# BMD-200_eval.net
KiCad netlist of a schematic drawn in EAGLE
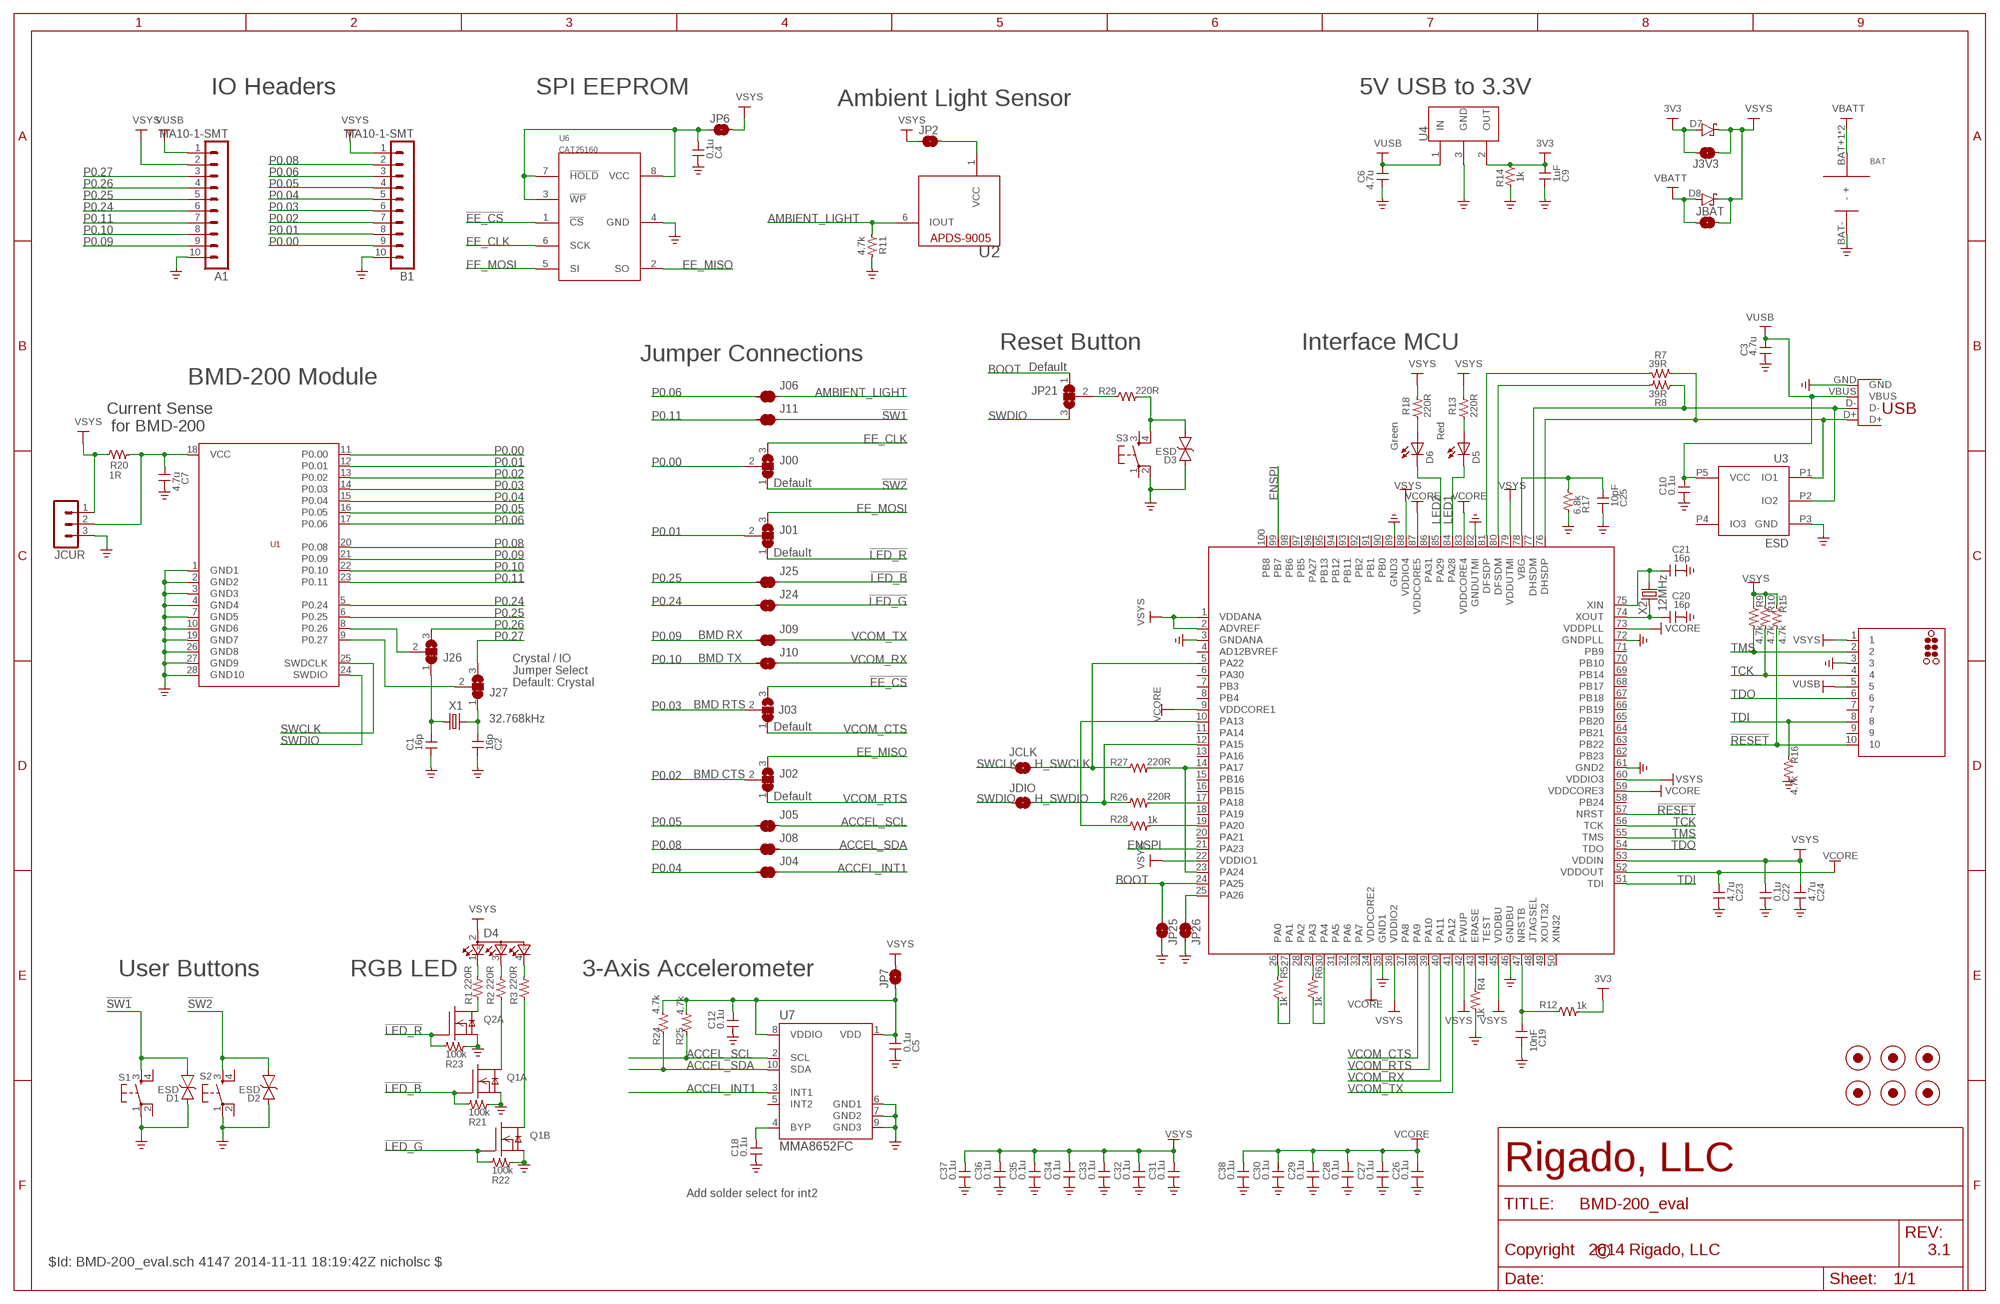
[diagram p0: schematic, sheet 1]

(export (version "E")
  (design (tool "Eeschema 10.0.6"))
  (components
    (comp (ref "A1")
      (value "MA10-1-SMT")
      (footprint "eagle-import:MA10-A-SMT")
      (description "10 SIL VERT SMT HDR")
      (fields (field (name "MFR") "Harwin"))
      (libsource (lib "eagle-import") (part "MA10-1-SMT"))
    )
    (comp (ref "B1")
      (value "MA10-1-SMT")
      (footprint "eagle-import:MA10-A-SMT")
      (description "10 SIL VERT SMT HDR")
      (fields (field (name "MFR") "Harwin"))
      (libsource (lib "eagle-import") (part "MA10-1-SMT"))
    )
    (comp (ref "BAT")
      (value "COINCELL-1")
      (footprint "eagle-import:CR2032-1")
      (description "Battery Holders, Clips & Contacts Linx CR2032 Battery Holder")
      (fields (field (name "MFR") "Linx"))
      (libsource (lib "eagle-import") (part "COINCELL-1"))
    )
    (comp (ref "C1")
      (value "16p")
      (footprint "eagle-import:SMD0402")
      (description "CAP CER 16PF 50V 5% NP0 0402")
      (fields (field (name "MFR") "Samsung"))
      (libsource (lib "eagle-import") (part "C-0402"))
    )
    (comp (ref "C2")
      (value "16p")
      (footprint "eagle-import:SMD0402")
      (description "CAP CER 16PF 50V 5% NP0 0402")
      (fields (field (name "MFR") "Samsung"))
      (libsource (lib "eagle-import") (part "C-0402"))
    )
    (comp (ref "C3")
      (value "4.7u")
      (footprint "eagle-import:SMD0603")
      (description "CAP CER 4.7UF 6.3V 10% X5R 0603")
      (fields (field (name "MFR") "Murata"))
      (libsource (lib "eagle-import") (part "C-0603"))
    )
    (comp (ref "C4")
      (value "0.1u")
      (footprint "eagle-import:SMD0402")
      (description "CAP CER 0.1UF 6.3V 10% X5R 0402")
      (fields (field (name "MFR") "Samsung"))
      (libsource (lib "eagle-import") (part "C-0402"))
    )
    (comp (ref "C5")
      (value "0.1u")
      (footprint "eagle-import:SMD0402")
      (description "CAP CER 0.1UF 6.3V 10% X5R 0402")
      (fields (field (name "MFR") "Samsung"))
      (libsource (lib "eagle-import") (part "C-0402"))
    )
    (comp (ref "C6")
      (value "4.7u")
      (footprint "eagle-import:SMD0603")
      (description "CAP CER 4.7UF 6.3V 10% X5R 0603")
      (fields (field (name "MFR") "Murata"))
      (libsource (lib "eagle-import") (part "C-0603"))
    )
    (comp (ref "C7")
      (value "4.7u")
      (footprint "eagle-import:SMD0603")
      (description "CAP CER 4.7UF 6.3V 10% X5R 0603")
      (fields (field (name "MFR") "Murata"))
      (libsource (lib "eagle-import") (part "C-0603"))
    )
    (comp (ref "C9")
      (value "1uF")
      (footprint "eagle-import:SMD0402")
      (description "CAP CER 1UF 6.3V 5% X5R 0402")
      (fields (field (name "MFR") "Samsung"))
      (libsource (lib "eagle-import") (part "C-0402"))
    )
    (comp (ref "C10")
      (value "0.1u")
      (footprint "eagle-import:SMD0402")
      (description "CAP CER 0.1UF 6.3V 10% X5R 0402")
      (fields (field (name "MFR") "Samsung"))
      (libsource (lib "eagle-import") (part "C-0402"))
    )
    (comp (ref "C12")
      (value "0.1u")
      (footprint "eagle-import:SMD0402")
      (description "CAP CER 0.1UF 6.3V 10% X5R 0402")
      (fields (field (name "MFR") "Samsung"))
      (libsource (lib "eagle-import") (part "C-0402"))
    )
    (comp (ref "C18")
      (value "0.1u")
      (footprint "eagle-import:SMD0402")
      (description "CAP CER 0.1UF 6.3V 10% X5R 0402")
      (fields (field (name "MFR") "Samsung"))
      (libsource (lib "eagle-import") (part "C-0402"))
    )
    (comp (ref "C19")
      (value "10nF")
      (footprint "eagle-import:SMD0402")
      (description "CAP CER 10000PF 16V 10% X7R 0402")
      (fields (field (name "MFR") "Samsung"))
      (libsource (lib "eagle-import") (part "C-0402"))
    )
    (comp (ref "C20")
      (value "16p")
      (footprint "eagle-import:SMD0402")
      (description "CAP CER 16PF 50V 5% NP0 0402")
      (fields (field (name "MFR") "Samsung"))
      (libsource (lib "eagle-import") (part "C-0402"))
    )
    (comp (ref "C21")
      (value "16p")
      (footprint "eagle-import:SMD0402")
      (description "CAP CER 16PF 50V 5% NP0 0402")
      (fields (field (name "MFR") "Samsung"))
      (libsource (lib "eagle-import") (part "C-0402"))
    )
    (comp (ref "C22")
      (value "0.1u")
      (footprint "eagle-import:SMD0402")
      (description "CAP CER 0.1UF 6.3V 10% X5R 0402")
      (fields (field (name "MFR") "Samsung"))
      (libsource (lib "eagle-import") (part "C-0402"))
    )
    (comp (ref "C23")
      (value "4.7u")
      (footprint "eagle-import:SMD0603")
      (description "CAP CER 4.7UF 6.3V 10% X5R 0603")
      (fields (field (name "MFR") "Murata"))
      (libsource (lib "eagle-import") (part "C-0603"))
    )
    (comp (ref "C24")
      (value "4.7u")
      (footprint "eagle-import:SMD0603")
      (description "CAP CER 4.7UF 6.3V 10% X5R 0603")
      (fields (field (name "MFR") "Murata"))
      (libsource (lib "eagle-import") (part "C-0603"))
    )
    (comp (ref "C25")
      (value "10pF")
      (footprint "eagle-import:SMD0402")
      (description "CAP CER 10PF 50V 5% NP0 0402")
      (fields (field (name "MFR") "Samsung"))
      (libsource (lib "eagle-import") (part "C-0402"))
    )
    (comp (ref "C26")
      (value "0.1u")
      (footprint "eagle-import:SMD0402")
      (description "CAP CER 0.1UF 6.3V 10% X5R 0402")
      (fields (field (name "MFR") "Samsung"))
      (libsource (lib "eagle-import") (part "C-0402"))
    )
    (comp (ref "C27")
      (value "0.1u")
      (footprint "eagle-import:SMD0402")
      (description "CAP CER 0.1UF 6.3V 10% X5R 0402")
      (fields (field (name "MFR") "Samsung"))
      (libsource (lib "eagle-import") (part "C-0402"))
    )
    (comp (ref "C28")
      (value "0.1u")
      (footprint "eagle-import:SMD0402")
      (description "CAP CER 0.1UF 6.3V 10% X5R 0402")
      (fields (field (name "MFR") "Samsung"))
      (libsource (lib "eagle-import") (part "C-0402"))
    )
    (comp (ref "C29")
      (value "0.1u")
      (footprint "eagle-import:SMD0402")
      (description "CAP CER 0.1UF 6.3V 10% X5R 0402")
      (fields (field (name "MFR") "Samsung"))
      (libsource (lib "eagle-import") (part "C-0402"))
    )
    (comp (ref "C30")
      (value "0.1u")
      (footprint "eagle-import:SMD0402")
      (description "CAP CER 0.1UF 6.3V 10% X5R 0402")
      (fields (field (name "MFR") "Samsung"))
      (libsource (lib "eagle-import") (part "C-0402"))
    )
    (comp (ref "C31")
      (value "0.1u")
      (footprint "eagle-import:SMD0402")
      (description "CAP CER 0.1UF 6.3V 10% X5R 0402")
      (fields (field (name "MFR") "Samsung"))
      (libsource (lib "eagle-import") (part "C-0402"))
    )
    (comp (ref "C32")
      (value "0.1u")
      (footprint "eagle-import:SMD0402")
      (description "CAP CER 0.1UF 6.3V 10% X5R 0402")
      (fields (field (name "MFR") "Samsung"))
      (libsource (lib "eagle-import") (part "C-0402"))
    )
    (comp (ref "C33")
      (value "0.1u")
      (footprint "eagle-import:SMD0402")
      (description "CAP CER 0.1UF 6.3V 10% X5R 0402")
      (fields (field (name "MFR") "Samsung"))
      (libsource (lib "eagle-import") (part "C-0402"))
    )
    (comp (ref "C34")
      (value "0.1u")
      (footprint "eagle-import:SMD0402")
      (description "CAP CER 0.1UF 6.3V 10% X5R 0402")
      (fields (field (name "MFR") "Samsung"))
      (libsource (lib "eagle-import") (part "C-0402"))
    )
    (comp (ref "C35")
      (value "0.1u")
      (footprint "eagle-import:SMD0402")
      (description "CAP CER 0.1UF 6.3V 10% X5R 0402")
      (fields (field (name "MFR") "Samsung"))
      (libsource (lib "eagle-import") (part "C-0402"))
    )
    (comp (ref "C36")
      (value "0.1u")
      (footprint "eagle-import:SMD0402")
      (description "CAP CER 0.1UF 6.3V 10% X5R 0402")
      (fields (field (name "MFR") "Samsung"))
      (libsource (lib "eagle-import") (part "C-0402"))
    )
    (comp (ref "C37")
      (value "0.1u")
      (footprint "eagle-import:SMD0402")
      (description "CAP CER 0.1UF 6.3V 10% X5R 0402")
      (fields (field (name "MFR") "Samsung"))
      (libsource (lib "eagle-import") (part "C-0402"))
    )
    (comp (ref "C38")
      (value "0.1u")
      (footprint "eagle-import:SMD0402")
      (description "CAP CER 0.1UF 6.3V 10% X5R 0402")
      (fields (field (name "MFR") "Samsung"))
      (libsource (lib "eagle-import") (part "C-0402"))
    )
    (comp (ref "D1")
      (value "ESD")
      (footprint "eagle-import:SOD-923")
      (description "TVS DIODE 3.3VWM SOD923")
      (fields
        (field (name "EACH") "0.04234")
        (field (name "MFPN") "ESD9B3.3ST5G")
        (field (name "MFR") "On Semi")
        (field (name "VEND") "Digikey")
        (field (name "VPN") "ESD9B3.3ST5GOSCT-ND")
      )
      (libsource (lib "eagle-import") (part "ESDSOD-923"))
    )
    (comp (ref "D2")
      (value "ESD")
      (footprint "eagle-import:SOD-923")
      (description "TVS DIODE 3.3VWM SOD923")
      (fields
        (field (name "EACH") "0.04234")
        (field (name "MFPN") "ESD9B3.3ST5G")
        (field (name "MFR") "On Semi")
        (field (name "VEND") "Digikey")
        (field (name "VPN") "ESD9B3.3ST5GOSCT-ND")
      )
      (libsource (lib "eagle-import") (part "ESDSOD-923"))
    )
    (comp (ref "D3")
      (value "ESD")
      (footprint "eagle-import:SOD-923")
      (description "TVS DIODE 3.3VWM SOD923")
      (fields
        (field (name "EACH") "0.04234")
        (field (name "MFPN") "ESD9B3.3ST5G")
        (field (name "MFR") "On Semi")
        (field (name "VEND") "Digikey")
        (field (name "VPN") "ESD9B3.3ST5GOSCT-ND")
      )
      (libsource (lib "eagle-import") (part "ESDSOD-923"))
    )
    (comp (ref "D4")
      (value "RGD_LED")
      (footprint "eagle-import:P-LLC-4-SMALL")
      (description "LED RGB SMD DIFF 4-PLCC")
      (fields (field (name "MFR") "Cree"))
      (libsource (lib "eagle-import") (part "TOPLED-3-MIN"))
    )
    (comp (ref "D5")
      (value "Red")
      (footprint "eagle-import:LED0603")
      (description "LED 1.6X0.8MM 625NM RED CLR SMD")
      (fields (field (name "MFR") "Kingbright"))
      (libsource (lib "eagle-import") (part "LED-0603"))
    )
    (comp (ref "D6")
      (value "Green")
      (footprint "eagle-import:LED0603")
      (description "LED 1.6X0.8MM 568NM GRN CLR SMD")
      (fields (field (name "MFR") "Kingbright"))
      (libsource (lib "eagle-import") (part "LED-0603"))
    )
    (comp (ref "D7")
      (value "D-SCHOTTKY-SOD-123")
      (footprint "eagle-import:SOD-123")
      (description "DIODE SCHOTTKY 20V 0.5A SOD123")
      (fields (field (name "MFR") "ON Semi"))
      (libsource (lib "eagle-import") (part "D-SCHOTTKY-SOD-123"))
    )
    (comp (ref "D8")
      (value "D-SCHOTTKY-SOD-123")
      (footprint "eagle-import:SOD-123")
      (description "DIODE SCHOTTKY 20V 0.5A SOD123")
      (fields (field (name "MFR") "ON Semi"))
      (libsource (lib "eagle-import") (part "D-SCHOTTKY-SOD-123"))
    )
    (comp (ref "FID1")
      (value "FIDUCIAL-.04")
      (footprint "eagle-import:FIDUCIAL-.04")
      (libsource (lib "eagle-import") (part "FIDUCIAL-.04"))
    )
    (comp (ref "FID2")
      (value "FIDUCIAL-.04")
      (footprint "eagle-import:FIDUCIAL-.04")
      (libsource (lib "eagle-import") (part "FIDUCIAL-.04"))
    )
    (comp (ref "FID3")
      (value "FIDUCIAL-.04")
      (footprint "eagle-import:FIDUCIAL-.04")
      (libsource (lib "eagle-import") (part "FIDUCIAL-.04"))
    )
    (comp (ref "FID4")
      (value "FIDUCIAL-.04")
      (footprint "eagle-import:FIDUCIAL-.04")
      (libsource (lib "eagle-import") (part "FIDUCIAL-.04"))
    )
    (comp (ref "FID5")
      (value "FIDUCIAL-.04")
      (footprint "eagle-import:FIDUCIAL-.04")
      (libsource (lib "eagle-import") (part "FIDUCIAL-.04"))
    )
    (comp (ref "FID6")
      (value "FIDUCIAL-.04")
      (footprint "eagle-import:FIDUCIAL-.04")
      (libsource (lib "eagle-import") (part "FIDUCIAL-.04"))
    )
    (comp (ref "J00")
      (value "SOLDER_JUMPER_2WAY-TRACE12")
      (footprint "eagle-import:SJ_2WAY_TRACE")
      (libsource (lib "eagle-import") (part "SOLDER_JUMPER_2WAY-TRACE12"))
    )
    (comp (ref "J01")
      (value "SOLDER_JUMPER_2WAY-TRACE12")
      (footprint "eagle-import:SJ_2WAY_TRACE")
      (libsource (lib "eagle-import") (part "SOLDER_JUMPER_2WAY-TRACE12"))
    )
    (comp (ref "J02")
      (value "SOLDER_JUMPER_2WAY-TRACE12")
      (footprint "eagle-import:SJ_2WAY_TRACE")
      (libsource (lib "eagle-import") (part "SOLDER_JUMPER_2WAY-TRACE12"))
    )
    (comp (ref "J03")
      (value "SOLDER_JUMPER_2WAY-TRACE12")
      (footprint "eagle-import:SJ_2WAY_TRACE")
      (libsource (lib "eagle-import") (part "SOLDER_JUMPER_2WAY-TRACE12"))
    )
    (comp (ref "J3V3")
      (value "SOLDER_JUMPER")
      (footprint "eagle-import:SJ_2")
      (libsource (lib "eagle-import") (part "SOLDER_JUMPER"))
    )
    (comp (ref "J04")
      (value "SOLDER_JUMPER-TRACE")
      (footprint "eagle-import:SJ_2_TRACE")
      (libsource (lib "eagle-import") (part "SOLDER_JUMPER-TRACE"))
    )
    (comp (ref "J05")
      (value "SOLDER_JUMPER-TRACE")
      (footprint "eagle-import:SJ_2_TRACE")
      (libsource (lib "eagle-import") (part "SOLDER_JUMPER-TRACE"))
    )
    (comp (ref "J06")
      (value "SOLDER_JUMPER-TRACE")
      (footprint "eagle-import:SJ_2_TRACE")
      (libsource (lib "eagle-import") (part "SOLDER_JUMPER-TRACE"))
    )
    (comp (ref "J08")
      (value "SOLDER_JUMPER-TRACE")
      (footprint "eagle-import:SJ_2_TRACE")
      (libsource (lib "eagle-import") (part "SOLDER_JUMPER-TRACE"))
    )
    (comp (ref "J09")
      (value "SOLDER_JUMPER-TRACE")
      (footprint "eagle-import:SJ_2_TRACE")
      (libsource (lib "eagle-import") (part "SOLDER_JUMPER-TRACE"))
    )
    (comp (ref "J10")
      (value "SOLDER_JUMPER-TRACE")
      (footprint "eagle-import:SJ_2_TRACE")
      (libsource (lib "eagle-import") (part "SOLDER_JUMPER-TRACE"))
    )
    (comp (ref "J11")
      (value "SOLDER_JUMPER-TRACE")
      (footprint "eagle-import:SJ_2_TRACE")
      (libsource (lib "eagle-import") (part "SOLDER_JUMPER-TRACE"))
    )
    (comp (ref "J24")
      (value "SOLDER_JUMPER-TRACE")
      (footprint "eagle-import:SJ_2_TRACE")
      (libsource (lib "eagle-import") (part "SOLDER_JUMPER-TRACE"))
    )
    (comp (ref "J25")
      (value "SOLDER_JUMPER-TRACE")
      (footprint "eagle-import:SJ_2_TRACE")
      (libsource (lib "eagle-import") (part "SOLDER_JUMPER-TRACE"))
    )
    (comp (ref "J26")
      (value "SOLDER_JUMPER_2WAY-TRACE12")
      (footprint "eagle-import:SJ_2WAY_TRACE")
      (libsource (lib "eagle-import") (part "SOLDER_JUMPER_2WAY-TRACE12"))
    )
    (comp (ref "J27")
      (value "SOLDER_JUMPER_2WAY-TRACE12")
      (footprint "eagle-import:SJ_2WAY_TRACE")
      (libsource (lib "eagle-import") (part "SOLDER_JUMPER_2WAY-TRACE12"))
    )
    (comp (ref "JBAT")
      (value "SOLDER_JUMPER")
      (footprint "eagle-import:SJ_2")
      (libsource (lib "eagle-import") (part "SOLDER_JUMPER"))
    )
    (comp (ref "JCLK")
      (value "SOLDER_JUMPER-TRACE")
      (footprint "eagle-import:SJ_2_TRACE")
      (libsource (lib "eagle-import") (part "SOLDER_JUMPER-TRACE"))
    )
    (comp (ref "JCUR")
      (value "MA03-1SMT")
      (footprint "eagle-import:MA03-1-SMT")
      (description "3POS SIL VERTICAL SMT HEADER")
      (fields (field (name "MFR") "Harwin"))
      (libsource (lib "eagle-import") (part "MA03-1SMT"))
    )
    (comp (ref "JDIO")
      (value "SOLDER_JUMPER-TRACE")
      (footprint "eagle-import:SJ_2_TRACE")
      (libsource (lib "eagle-import") (part "SOLDER_JUMPER-TRACE"))
    )
    (comp (ref "JP2")
      (value "SOLDER_JUMPER-TRACE")
      (footprint "eagle-import:SJ_2_TRACE")
      (libsource (lib "eagle-import") (part "SOLDER_JUMPER-TRACE"))
    )
    (comp (ref "JP6")
      (value "SOLDER_JUMPER")
      (footprint "eagle-import:SJ_2")
      (libsource (lib "eagle-import") (part "SOLDER_JUMPER"))
    )
    (comp (ref "JP7")
      (value "SOLDER_JUMPER-TRACE")
      (footprint "eagle-import:SJ_2_TRACE")
      (libsource (lib "eagle-import") (part "SOLDER_JUMPER-TRACE"))
    )
    (comp (ref "JP21")
      (value "SOLDER_JUMPER_2WAY-TRACE12")
      (footprint "eagle-import:SJ_2WAY_TRACE")
      (libsource (lib "eagle-import") (part "SOLDER_JUMPER_2WAY-TRACE12"))
    )
    (comp (ref "JP25")
      (value "SOLDER_JUMPER")
      (footprint "eagle-import:SJ_2")
      (libsource (lib "eagle-import") (part "SOLDER_JUMPER"))
    )
    (comp (ref "JP26")
      (value "SOLDER_JUMPER")
      (footprint "eagle-import:SJ_2")
      (libsource (lib "eagle-import") (part "SOLDER_JUMPER"))
    )
    (comp (ref "JTAG")
      (value "TC2050-NL")
      (footprint "eagle-import:TC2050-MCP-NL")
      (libsource (lib "eagle-import") (part "TC2050-NL"))
    )
    (comp (ref "JUSB")
      (value "USB-MICROB-2")
      (footprint "eagle-import:USB-MICROB-2")
      (description "CONN USB MICRO B RECPT SMT R/A")
      (fields (field (name "MFR") "FCI"))
      (libsource (lib "eagle-import") (part "USB-MICROB-2"))
    )
    (comp (ref "Q1")
      (value "DUAL-NFET-SOT563")
      (footprint "eagle-import:SOT-563")
      (description "MOSFET 2N-CH 20V 0.18A ES6")
      (fields
        (field (name "MFR") "Toshiba")
        (field (name "EACH") "0.0988")
        (field (name "MFPN") "SSM6N35FE,LM")
        (field (name "VEND") "Digikey")
        (field (name "VPN") "SSM6N35FELMCT-ND")
      )
      (libsource (lib "eagle-import") (part "DUAL-NFET-SOT563"))
    )
    (comp (ref "Q2")
      (value "DUAL-NFET-SOT563")
      (footprint "eagle-import:SOT-563")
      (description "MOSFET 2N-CH 20V 0.18A ES7")
      (fields (field (name "MFR") "Toshiba"))
      (libsource (lib "eagle-import") (part "DUAL-NFET-SOT563"))
    )
    (comp (ref "R1")
      (value "220R")
      (footprint "eagle-import:SMD0402")
      (description "RES 220 OHM 1/16W 5% 0402")
      (fields (field (name "MFR") "Samsung"))
      (libsource (lib "eagle-import") (part "R-0402"))
    )
    (comp (ref "R2")
      (value "220R")
      (footprint "eagle-import:SMD0402")
      (description "RES 220 OHM 1/16W 5% 0402")
      (fields (field (name "MFR") "Samsung"))
      (libsource (lib "eagle-import") (part "R-0402"))
    )
    (comp (ref "R3")
      (value "220R")
      (footprint "eagle-import:SMD0402")
      (description "RES 220 OHM 1/16W 5% 0402")
      (fields (field (name "MFR") "Samsung"))
      (libsource (lib "eagle-import") (part "R-0402"))
    )
    (comp (ref "R4")
      (value "1k")
      (footprint "eagle-import:SMD0402")
      (description "RES 1K OHM 1/16W 5% 0402")
      (fields (field (name "MFR") "Samsung"))
      (libsource (lib "eagle-import") (part "R-0402"))
    )
    (comp (ref "R5")
      (value "1k")
      (footprint "eagle-import:SMD0402")
      (description "RES 1K OHM 1/16W 5% 0402")
      (fields (field (name "MFR") "Samsung"))
      (libsource (lib "eagle-import") (part "R-0402"))
    )
    (comp (ref "R6")
      (value "1k")
      (footprint "eagle-import:SMD0402")
      (description "RES 1K OHM 1/16W 5% 0402")
      (fields (field (name "MFR") "Samsung"))
      (libsource (lib "eagle-import") (part "R-0402"))
    )
    (comp (ref "R7")
      (value "39R")
      (footprint "eagle-import:SMD0402")
      (description "RES 39 OHM 1/16W 5% 0402")
      (fields (field (name "MFR") "Samsung"))
      (libsource (lib "eagle-import") (part "R-0402"))
    )
    (comp (ref "R8")
      (value "39R")
      (footprint "eagle-import:SMD0402")
      (description "RES 39 OHM 1/16W 5% 0402")
      (fields (field (name "MFR") "Samsung"))
      (libsource (lib "eagle-import") (part "R-0402"))
    )
    (comp (ref "R9")
      (value "4.7k")
      (footprint "eagle-import:SMD0402")
      (description "RES 4.7K OHM 1/16W 5% 0402")
      (fields (field (name "MFR") "Samsung"))
      (libsource (lib "eagle-import") (part "R-0402"))
    )
    (comp (ref "R10")
      (value "4.7k")
      (footprint "eagle-import:SMD0402")
      (description "RES 4.7K OHM 1/16W 5% 0402")
      (fields (field (name "MFR") "Samsung"))
      (libsource (lib "eagle-import") (part "R-0402"))
    )
    (comp (ref "R11")
      (value "4.7k")
      (footprint "eagle-import:SMD0402")
      (description "RES 4.7K OHM 1/16W 5% 0402")
      (fields (field (name "MFR") "Samsung"))
      (libsource (lib "eagle-import") (part "R-0402"))
    )
    (comp (ref "R12")
      (value "1k")
      (footprint "eagle-import:SMD0402")
      (description "RES 1K OHM 1/16W 5% 0402")
      (fields (field (name "MFR") "Samsung"))
      (libsource (lib "eagle-import") (part "R-0402"))
    )
    (comp (ref "R13")
      (value "220R")
      (footprint "eagle-import:SMD0402")
      (description "RES 220 OHM 1/16W 5% 0402")
      (fields (field (name "MFR") "Samsung"))
      (libsource (lib "eagle-import") (part "R-0402"))
    )
    (comp (ref "R14")
      (value "1k")
      (footprint "eagle-import:SMD0402")
      (description "RES 1K OHM 1/16W 5% 0402")
      (fields (field (name "MFR") "Samsung"))
      (libsource (lib "eagle-import") (part "R-0402"))
    )
    (comp (ref "R15")
      (value "4.7k")
      (footprint "eagle-import:SMD0402")
      (description "RES 4.7K OHM 1/16W 5% 0402")
      (fields (field (name "MFR") "Samsung"))
      (libsource (lib "eagle-import") (part "R-0402"))
    )
    (comp (ref "R16")
      (value "4.7k")
      (footprint "eagle-import:SMD0402")
      (description "RES 4.7K OHM 1/16W 5% 0402")
      (fields (field (name "MFR") "Samsung"))
      (libsource (lib "eagle-import") (part "R-0402"))
    )
    (comp (ref "R17")
      (value "6.8k")
      (footprint "eagle-import:SMD0402")
      (description "RES 6.8K OHM 1/16W 1% 0402")
      (fields (field (name "MFR") "Samsung"))
      (libsource (lib "eagle-import") (part "R-0402"))
    )
    (comp (ref "R18")
      (value "220R")
      (footprint "eagle-import:SMD0402")
      (description "RES 220 OHM 1/16W 5% 0402")
      (fields (field (name "MFR") "Samsung"))
      (libsource (lib "eagle-import") (part "R-0402"))
    )
    (comp (ref "R20")
      (value "1R")
      (footprint "eagle-import:SMD0805")
      (description "RES 1.00 OHM 1/8W 1% 0805 SMD")
      (fields (field (name "MFR") "Yageo"))
      (libsource (lib "eagle-import") (part "R-0805"))
    )
    (comp (ref "R21")
      (value "100k")
      (footprint "eagle-import:SMD0402")
      (description "RES 100K OHM 1/16W 5% 0402")
      (fields (field (name "MFR") "Samsung"))
      (libsource (lib "eagle-import") (part "R-0402"))
    )
    (comp (ref "R22")
      (value "100k")
      (footprint "eagle-import:SMD0402")
      (description "RES 100K OHM 1/16W 5% 0402")
      (fields (field (name "MFR") "Samsung"))
      (libsource (lib "eagle-import") (part "R-0402"))
    )
    (comp (ref "R23")
      (value "100k")
      (footprint "eagle-import:SMD0402")
      (description "RES 100K OHM 1/16W 5% 0402")
      (fields (field (name "MFR") "Samsung"))
      (libsource (lib "eagle-import") (part "R-0402"))
    )
    (comp (ref "R24")
      (value "4.7k")
      (footprint "eagle-import:SMD0402")
      (description "RES 4.7K OHM 1/16W 5% 0402")
      (fields (field (name "MFR") "Samsung"))
      (libsource (lib "eagle-import") (part "R-0402"))
    )
    (comp (ref "R25")
      (value "4.7k")
      (footprint "eagle-import:SMD0402")
      (description "RES 4.7K OHM 1/16W 5% 0402")
      (fields (field (name "MFR") "Samsung"))
      (libsource (lib "eagle-import") (part "R-0402"))
    )
    (comp (ref "R26")
      (value "220R")
      (footprint "eagle-import:SMD0402")
      (description "RES 220 OHM 1/16W 5% 0403")
      (fields (field (name "MFR") "Samsung"))
      (libsource (lib "eagle-import") (part "R-0402"))
    )
    (comp (ref "R27")
      (value "220R")
      (footprint "eagle-import:SMD0402")
      (description "RES 220 OHM 1/16W 5% 0404")
      (fields (field (name "MFR") "Samsung"))
      (libsource (lib "eagle-import") (part "R-0402"))
    )
    (comp (ref "R28")
      (value "1k")
      (footprint "eagle-import:SMD0402")
      (description "RES 1K OHM 1/16W 5% 0402")
      (fields (field (name "MFR") "Samsung"))
      (libsource (lib "eagle-import") (part "R-0402"))
    )
    (comp (ref "R29")
      (value "220R")
      (footprint "eagle-import:SMD0402")
      (description "RES 220 OHM 1/16W 5% 0405")
      (fields (field (name "MFR") "Samsung"))
      (libsource (lib "eagle-import") (part "R-0402"))
    )
    (comp (ref "S1")
      (value "10-XXTL3301-GW")
      (footprint "eagle-import:ESWITCH-TL3301-GW")
      (description "SWITCH TACTILE SPST-NO 0.05A 12V")
      (fields (field (name "MFR") "E-Switch"))
      (libsource (lib "eagle-import") (part "10-XXTL3301-GW"))
    )
    (comp (ref "S2")
      (value "10-XXTL3301-GW")
      (footprint "eagle-import:ESWITCH-TL3301-GW")
      (description "SWITCH TACTILE SPST-NO 0.05A 12V")
      (fields (field (name "MFR") "E-Switch"))
      (libsource (lib "eagle-import") (part "10-XXTL3301-GW"))
    )
    (comp (ref "S3")
      (value "10-XXTL3301-GW")
      (footprint "eagle-import:ESWITCH-TL3301-GW")
      (description "SWITCH TACTILE SPST-NO 0.05A 12V")
      (fields (field (name "MFR") "E-Switch"))
      (libsource (lib "eagle-import") (part "10-XXTL3301-GW"))
    )
    (comp (ref "U1")
      (value "BMD-200")
      (footprint "eagle-import:BMD-200")
      (description "BLE Module w/ nRF51822 SoC")
      (fields (field (name "MFR") "Rigado"))
      (libsource (lib "eagle-import") (part "BMD-200"))
    )
    (comp (ref "U2")
      (value "APDS9005")
      (footprint "eagle-import:APDS9005")
      (description "AMBIENT LIGHT SENSOR 6CHIPLED")
      (fields (field (name "MFR") "Avago"))
      (libsource (lib "eagle-import") (part "APDS9005"))
    )
    (comp (ref "U3")
      (value "ESD")
      (footprint "eagle-import:TPD3E001")
      (description "TVS DIODE SOT5")
      (fields (field (name "MFR") "TI"))
      (libsource (lib "eagle-import") (part "TPD3E001"))
    )
    (comp (ref "U4")
      (value "VREG-SOT23")
      (footprint "eagle-import:SOT-23-3")
      (description "IC REG LDO 3.3V 0.3A SOT23-3")
      (fields
        (field (name "EACH") "0.144")
        (field (name "MFPN") "AP7333-33SAG-7")
        (field (name "MFR") "Diodes Incorporated")
        (field (name "VEND") "Digikey")
        (field (name "VPN") "AP7333-33SAG-7DICT-ND")
      )
      (libsource (lib "eagle-import") (part "VREG-SOT23"))
    )
    (comp (ref "U6")
      (value "CAT25160")
      (footprint "eagle-import:SOIC-8N")
      (description "IC EEPROM 16KBIT 20MHZ 8SOIC")
      (fields (field (name "MFR") "ON Semi"))
      (libsource (lib "eagle-import") (part "CAT25512"))
    )
    (comp (ref "U7")
      (value "MMA8652FC")
      (footprint "eagle-import:DFN-10_2X2")
      (description "IC ACCELEROMETER 3AXIS 10DFN")
      (fields (field (name "MFR") "Freescale"))
      (libsource (lib "eagle-import") (part "MMA8652FC"))
    )
    (comp (ref "U8")
      (value "ATSAM3C-TQFP")
      (footprint "eagle-import:TQFP100")
      (description "IC MCU 32BIT 128KB FLASH 100LQFP")
      (fields (field (name "MFR") "Atmel"))
      (libsource (lib "eagle-import") (part "ATSAM3C-TQFP"))
    )
    (comp (ref "X1")
      (value "32.768kHz")
      (footprint "eagle-import:2SMD")
      (description "CRYSTAL 32.768KHZ 12.5PF SMD")
      (fields
        (field (name "EACH") "0.36")
        (field (name "MFPN") "ST3215SB32768H5HPWAA")
        (field (name "MFR") "AVX")
        (field (name "VEND") "Digikey")
        (field (name "VPN") "478-5428-1-ND")
      )
      (libsource (lib "eagle-import") (part "CRYSTAL2SMD"))
    )
    (comp (ref "X2")
      (value "12MHz")
      (footprint "eagle-import:3225")
      (description "CRYSTAL 12MHZ 18PF SMD")
      (fields (field (name "MFR") "TXC"))
      (libsource (lib "eagle-import") (part "CRYSTAL-3.2X2.5MM"))
    )
  )
  (nets
    (net (code "1") (name "/ACCEL_INT1") (class "Default")
      (node (ref "J04") (pin "2") (pinfunction "2_2") (pintype "passive"))
      (node (ref "U7") (pin "3") (pinfunction "INT1_3") (pintype "bidirectional"))
    )
    (net (code "2") (name "/ACCEL_SCL") (class "Default")
      (node (ref "J05") (pin "2") (pinfunction "2_2") (pintype "passive"))
      (node (ref "R25") (pin "1") (pinfunction "1_1") (pintype "passive"))
      (node (ref "U7") (pin "2") (pinfunction "SCL_2") (pintype "bidirectional"))
    )
    (net (code "3") (name "/ACCEL_SDA") (class "Default")
      (node (ref "J08") (pin "2") (pinfunction "2_2") (pintype "passive"))
      (node (ref "R24") (pin "1") (pinfunction "1_1") (pintype "passive"))
      (node (ref "U7") (pin "10") (pinfunction "SDA_10") (pintype "bidirectional"))
    )
    (net (code "4") (name "/AMBIENT_LIGHT") (class "Default")
      (node (ref "J06") (pin "2") (pinfunction "2_2") (pintype "passive"))
      (node (ref "R11") (pin "1") (pinfunction "1_1") (pintype "passive"))
      (node (ref "U2") (pin "6") (pinfunction "IOUT_6") (pintype "output"))
    )
    (net (code "5") (name "/BOOT") (class "Default")
      (node (ref "JP21") (pin "1") (pinfunction "1_1") (pintype "passive"))
      (node (ref "JP25") (pin "1") (pinfunction "1_1") (pintype "passive"))
      (node (ref "U8") (pin "24") (pinfunction "PA25_24") (pintype "bidirectional"))
    )
    (net (code "6") (name "/EE_CLK") (class "Default")
      (node (ref "J00") (pin "3") (pinfunction "3_3") (pintype "passive"))
      (node (ref "U6") (pin "6") (pinfunction "SCK_6") (pintype "input"))
    )
    (net (code "7") (name "/EE_MISO") (class "Default")
      (node (ref "J02") (pin "3") (pinfunction "3_3") (pintype "passive"))
      (node (ref "U6") (pin "2") (pinfunction "SO_2") (pintype "output"))
    )
    (net (code "8") (name "/EE_MOSI") (class "Default")
      (node (ref "J01") (pin "3") (pinfunction "3_3") (pintype "passive"))
      (node (ref "U6") (pin "5") (pinfunction "SI_5") (pintype "input"))
    )
    (net (code "9") (name "/ENSPI") (class "Default")
      (node (ref "U8") (pin "21") (pinfunction "PA23_21") (pintype "bidirectional"))
      (node (ref "U8") (pin "99") (pinfunction "PB7_99") (pintype "bidirectional"))
    )
    (net (code "10") (name "/H_SWCLK") (class "Default")
      (node (ref "JCLK") (pin "1") (pinfunction "1_1") (pintype "passive"))
      (node (ref "R27") (pin "1") (pinfunction "1_1") (pintype "passive"))
      (node (ref "U8") (pin "5") (pinfunction "PA22_5") (pintype "bidirectional"))
    )
    (net (code "11") (name "/H_SWDIO") (class "Default")
      (node (ref "JDIO") (pin "1") (pinfunction "1_1") (pintype "passive"))
      (node (ref "R26") (pin "1") (pinfunction "1_1") (pintype "passive"))
      (node (ref "U8") (pin "12") (pinfunction "PA15_12") (pintype "bidirectional"))
    )
    (net (code "12") (name "/LED1") (class "Default")
      (node (ref "D5") (pin "C") (pinfunction "C_C") (pintype "passive"))
      (node (ref "U8") (pin "84") (pinfunction "PA28_84") (pintype "bidirectional"))
    )
    (net (code "13") (name "/LED2") (class "Default")
      (node (ref "D6") (pin "C") (pinfunction "C_C") (pintype "passive"))
      (node (ref "U8") (pin "85") (pinfunction "PA29_85") (pintype "bidirectional"))
    )
    (net (code "14") (name "/P0.00") (class "Default")
      (node (ref "B1") (pin "9") (pinfunction "9_9") (pintype "passive"))
      (node (ref "J00") (pin "2") (pinfunction "2_2") (pintype "passive"))
      (node (ref "U1") (pin "11") (pinfunction "P0.00_11") (pintype "bidirectional"))
    )
    (net (code "15") (name "/P0.01") (class "Default")
      (node (ref "B1") (pin "8") (pinfunction "8_8") (pintype "passive"))
      (node (ref "J01") (pin "2") (pinfunction "2_2") (pintype "passive"))
      (node (ref "U1") (pin "12") (pinfunction "P0.01_12") (pintype "bidirectional"))
    )
    (net (code "16") (name "/P0.02") (class "Default")
      (node (ref "B1") (pin "7") (pinfunction "7_7") (pintype "passive"))
      (node (ref "J02") (pin "2") (pinfunction "2_2") (pintype "passive"))
      (node (ref "U1") (pin "13") (pinfunction "P0.02_13") (pintype "bidirectional"))
    )
    (net (code "17") (name "/P0.03") (class "Default")
      (node (ref "B1") (pin "6") (pinfunction "6_6") (pintype "passive"))
      (node (ref "J03") (pin "2") (pinfunction "2_2") (pintype "passive"))
      (node (ref "U1") (pin "14") (pinfunction "P0.03_14") (pintype "bidirectional"))
    )
    (net (code "18") (name "/P0.04") (class "Default")
      (node (ref "B1") (pin "5") (pinfunction "5_5") (pintype "passive"))
      (node (ref "J04") (pin "1") (pinfunction "1_1") (pintype "passive"))
      (node (ref "U1") (pin "15") (pinfunction "P0.04_15") (pintype "bidirectional"))
    )
    (net (code "19") (name "/P0.05") (class "Default")
      (node (ref "B1") (pin "4") (pinfunction "4_4") (pintype "passive"))
      (node (ref "J05") (pin "1") (pinfunction "1_1") (pintype "passive"))
      (node (ref "U1") (pin "16") (pinfunction "P0.05_16") (pintype "bidirectional"))
    )
    (net (code "20") (name "/P0.06") (class "Default")
      (node (ref "B1") (pin "3") (pinfunction "3_3") (pintype "passive"))
      (node (ref "J06") (pin "1") (pinfunction "1_1") (pintype "passive"))
      (node (ref "U1") (pin "17") (pinfunction "P0.06_17") (pintype "bidirectional"))
    )
    (net (code "21") (name "/P0.08") (class "Default")
      (node (ref "B1") (pin "2") (pinfunction "2_2") (pintype "passive"))
      (node (ref "J08") (pin "1") (pinfunction "1_1") (pintype "passive"))
      (node (ref "U1") (pin "20") (pinfunction "P0.08_20") (pintype "bidirectional"))
    )
    (net (code "22") (name "/P0.09") (class "Default")
      (node (ref "A1") (pin "9") (pinfunction "9_9") (pintype "passive"))
      (node (ref "J09") (pin "1") (pinfunction "1_1") (pintype "passive"))
      (node (ref "U1") (pin "21") (pinfunction "P0.09_21") (pintype "bidirectional"))
    )
    (net (code "23") (name "/P0.10") (class "Default")
      (node (ref "A1") (pin "8") (pinfunction "8_8") (pintype "passive"))
      (node (ref "J10") (pin "1") (pinfunction "1_1") (pintype "passive"))
      (node (ref "U1") (pin "22") (pinfunction "P0.10_22") (pintype "bidirectional"))
    )
    (net (code "24") (name "/P0.11") (class "Default")
      (node (ref "A1") (pin "7") (pinfunction "7_7") (pintype "passive"))
      (node (ref "J11") (pin "1") (pinfunction "1_1") (pintype "passive"))
      (node (ref "U1") (pin "23") (pinfunction "P0.11_23") (pintype "bidirectional"))
    )
    (net (code "25") (name "/P0.24") (class "Default")
      (node (ref "A1") (pin "6") (pinfunction "6_6") (pintype "passive"))
      (node (ref "J24") (pin "1") (pinfunction "1_1") (pintype "passive"))
      (node (ref "U1") (pin "5") (pinfunction "P0.24_5") (pintype "bidirectional"))
    )
    (net (code "26") (name "/P0.25") (class "Default")
      (node (ref "A1") (pin "5") (pinfunction "5_5") (pintype "passive"))
      (node (ref "J25") (pin "1") (pinfunction "1_1") (pintype "passive"))
      (node (ref "U1") (pin "6") (pinfunction "P0.25_6") (pintype "bidirectional"))
    )
    (net (code "27") (name "/P0.26") (class "Default")
      (node (ref "A1") (pin "4") (pinfunction "4_4") (pintype "passive"))
      (node (ref "J26") (pin "3") (pinfunction "3_3") (pintype "passive"))
    )
    (net (code "28") (name "/P0.27") (class "Default")
      (node (ref "A1") (pin "3") (pinfunction "3_3") (pintype "passive"))
      (node (ref "J27") (pin "3") (pinfunction "3_3") (pintype "passive"))
    )
    (net (code "29") (name "/SWCLK") (class "Default")
      (node (ref "JCLK") (pin "2") (pinfunction "2_2") (pintype "passive"))
      (node (ref "U1") (pin "25") (pinfunction "SWDCLK_25") (pintype "bidirectional"))
    )
    (net (code "30") (name "/SWDIO") (class "Default")
      (node (ref "JDIO") (pin "2") (pinfunction "2_2") (pintype "passive"))
      (node (ref "JP21") (pin "3") (pinfunction "3_3") (pintype "passive"))
      (node (ref "U1") (pin "24") (pinfunction "SWDIO_24") (pintype "bidirectional"))
    )
    (net (code "31") (name "/TCK") (class "Default")
      (node (ref "JTAG") (pin "4") (pinfunction "4_4") (pintype "passive"))
      (node (ref "R10") (pin "2") (pinfunction "2_2") (pintype "passive"))
      (node (ref "U8") (pin "56") (pinfunction "TCK_56") (pintype "bidirectional"))
    )
    (net (code "32") (name "/TDI") (class "Default")
      (node (ref "JTAG") (pin "8") (pinfunction "8_8") (pintype "passive"))
      (node (ref "R16") (pin "1") (pinfunction "1_1") (pintype "passive"))
      (node (ref "U8") (pin "51") (pinfunction "TDI_51") (pintype "bidirectional"))
    )
    (net (code "33") (name "/TDO") (class "Default")
      (node (ref "JTAG") (pin "6") (pinfunction "6_6") (pintype "passive"))
      (node (ref "U8") (pin "54") (pinfunction "TDO_54") (pintype "bidirectional"))
    )
    (net (code "34") (name "/TMS") (class "Default")
      (node (ref "JTAG") (pin "2") (pinfunction "2_2") (pintype "passive"))
      (node (ref "R9") (pin "2") (pinfunction "2_2") (pintype "passive"))
      (node (ref "U8") (pin "55") (pinfunction "TMS_55") (pintype "bidirectional"))
    )
    (net (code "35") (name "/VCOM_CTS") (class "Default")
      (node (ref "J03") (pin "1") (pinfunction "1_1") (pintype "passive"))
      (node (ref "U8") (pin "38") (pinfunction "PA9_38") (pintype "bidirectional"))
    )
    (net (code "36") (name "/VCOM_RTS") (class "Default")
      (node (ref "J02") (pin "1") (pinfunction "1_1") (pintype "passive"))
      (node (ref "U8") (pin "39") (pinfunction "PA10_39") (pintype "bidirectional"))
    )
    (net (code "37") (name "/VCOM_RX") (class "Default")
      (node (ref "J10") (pin "2") (pinfunction "2_2") (pintype "passive"))
      (node (ref "U8") (pin "40") (pinfunction "PA11_40") (pintype "bidirectional"))
    )
    (net (code "38") (name "/VCOM_TX") (class "Default")
      (node (ref "J09") (pin "2") (pinfunction "2_2") (pintype "passive"))
      (node (ref "U8") (pin "41") (pinfunction "PA12_41") (pintype "bidirectional"))
    )
    (net (code "39") (name "/~{EE_CS}") (class "Default")
      (node (ref "J03") (pin "3") (pinfunction "3_3") (pintype "passive"))
      (node (ref "U6") (pin "1") (pinfunction "~{CS}_1") (pintype "input"))
    )
    (net (code "40") (name "/~{LED_B}") (class "Default")
      (node (ref "J25") (pin "2") (pinfunction "2_2") (pintype "passive"))
      (node (ref "Q1") (pin "2") (pinfunction "G_2") (pintype "passive"))
      (node (ref "R21") (pin "2") (pinfunction "2_2") (pintype "passive"))
    )
    (net (code "41") (name "/~{LED_G}") (class "Default")
      (node (ref "J24") (pin "2") (pinfunction "2_2") (pintype "passive"))
      (node (ref "Q1") (pin "5") (pinfunction "G_5") (pintype "passive"))
      (node (ref "R22") (pin "2") (pinfunction "2_2") (pintype "passive"))
    )
    (net (code "42") (name "/~{LED_R}") (class "Default")
      (node (ref "J01") (pin "1") (pinfunction "1_1") (pintype "passive"))
      (node (ref "Q2") (pin "2") (pinfunction "G_2") (pintype "passive"))
      (node (ref "R23") (pin "2") (pinfunction "2_2") (pintype "passive"))
    )
    (net (code "43") (name "/~{RESET}") (class "Default")
      (node (ref "JTAG") (pin "10") (pinfunction "10_10") (pintype "passive"))
      (node (ref "R15") (pin "2") (pinfunction "2_2") (pintype "passive"))
      (node (ref "U8") (pin "57") (pinfunction "NRST_57") (pintype "bidirectional"))
    )
    (net (code "44") (name "/~{SW1}") (class "Default")
      (node (ref "D1") (pin "C") (pinfunction "C_C") (pintype "passive"))
      (node (ref "J11") (pin "2") (pinfunction "2_2") (pintype "passive"))
      (node (ref "S1") (pin "3") (pinfunction "S_3") (pintype "passive"))
    )
    (net (code "45") (name "/~{SW2}") (class "Default")
      (node (ref "D2") (pin "C") (pinfunction "C_C") (pintype "passive"))
      (node (ref "J00") (pin "1") (pinfunction "1_1") (pintype "passive"))
      (node (ref "S2") (pin "3") (pinfunction "S_3") (pintype "passive"))
    )
    (net (code "46") (name "3V3") (class "Default")
      (node (ref "C9") (pin "2") (pinfunction "3_2") (pintype "passive"))
      (node (ref "D7") (pin "A") (pinfunction "A_A") (pintype "passive"))
      (node (ref "J3V3") (pin "2") (pinfunction "2_2") (pintype "passive"))
      (node (ref "R12") (pin "2") (pinfunction "2_2") (pintype "passive"))
      (node (ref "R14") (pin "1") (pinfunction "1_1") (pintype "passive"))
      (node (ref "U4") (pin "2") (pinfunction "OUT_2") (pintype "power_in"))
    )
    (net (code "47") (name "GND") (class "Default")
      (node (ref "A1") (pin "10") (pinfunction "10_10") (pintype "passive"))
      (node (ref "B1") (pin "10") (pinfunction "10_10") (pintype "passive"))
      (node (ref "BAT") (pin "BAT-") (pinfunction "-_BAT-") (pintype "bidirectional"))
      (node (ref "C1") (pin "1") (pinfunction "1_1") (pintype "passive"))
      (node (ref "C10") (pin "1") (pinfunction "1_1") (pintype "passive"))
      (node (ref "C12") (pin "1") (pinfunction "1_1") (pintype "passive"))
      (node (ref "C18") (pin "1") (pinfunction "1_1") (pintype "passive"))
      (node (ref "C19") (pin "2") (pinfunction "3_2") (pintype "passive"))
      (node (ref "C2") (pin "1") (pinfunction "1_1") (pintype "passive"))
      (node (ref "C20") (pin "1") (pinfunction "1_1") (pintype "passive"))
      (node (ref "C21") (pin "1") (pinfunction "1_1") (pintype "passive"))
      (node (ref "C22") (pin "1") (pinfunction "1_1") (pintype "passive"))
      (node (ref "C23") (pin "1") (pinfunction "1_1") (pintype "passive"))
      (node (ref "C24") (pin "1") (pinfunction "1_1") (pintype "passive"))
      (node (ref "C25") (pin "1") (pinfunction "1_1") (pintype "passive"))
      (node (ref "C26") (pin "1") (pinfunction "1_1") (pintype "passive"))
      (node (ref "C27") (pin "1") (pinfunction "1_1") (pintype "passive"))
      (node (ref "C28") (pin "1") (pinfunction "1_1") (pintype "passive"))
      (node (ref "C29") (pin "1") (pinfunction "1_1") (pintype "passive"))
      (node (ref "C3") (pin "1") (pinfunction "1_1") (pintype "passive"))
      (node (ref "C30") (pin "1") (pinfunction "1_1") (pintype "passive"))
      (node (ref "C31") (pin "1") (pinfunction "1_1") (pintype "passive"))
      (node (ref "C32") (pin "1") (pinfunction "1_1") (pintype "passive"))
      (node (ref "C33") (pin "1") (pinfunction "1_1") (pintype "passive"))
      (node (ref "C34") (pin "1") (pinfunction "1_1") (pintype "passive"))
      (node (ref "C35") (pin "1") (pinfunction "1_1") (pintype "passive"))
      (node (ref "C36") (pin "1") (pinfunction "1_1") (pintype "passive"))
      (node (ref "C37") (pin "1") (pinfunction "1_1") (pintype "passive"))
      (node (ref "C38") (pin "1") (pinfunction "1_1") (pintype "passive"))
      (node (ref "C4") (pin "1") (pinfunction "1_1") (pintype "passive"))
      (node (ref "C5") (pin "1") (pinfunction "1_1") (pintype "passive"))
      (node (ref "C6") (pin "2") (pinfunction "3_2") (pintype "passive"))
      (node (ref "C7") (pin "2") (pinfunction "3_2") (pintype "passive"))
      (node (ref "C9") (pin "1") (pinfunction "1_1") (pintype "passive"))
      (node (ref "D1") (pin "A") (pinfunction "A_A") (pintype "passive"))
      (node (ref "D2") (pin "A") (pinfunction "A_A") (pintype "passive"))
      (node (ref "D3") (pin "A") (pinfunction "A_A") (pintype "passive"))
      (node (ref "JCUR") (pin "3") (pinfunction "3_3") (pintype "passive"))
      (node (ref "JP25") (pin "2") (pinfunction "2_2") (pintype "passive"))
      (node (ref "JP26") (pin "2") (pinfunction "2_2") (pintype "passive"))
      (node (ref "JTAG") (pin "3") (pinfunction "3_3") (pintype "passive"))
      (node (ref "JUSB") (pin "GND") (pinfunction "GND_GND") (pintype "bidirectional"))
      (node (ref "Q1") (pin "1") (pinfunction "S_1") (pintype "passive"))
      (node (ref "Q1") (pin "4") (pinfunction "S_4") (pintype "passive"))
      (node (ref "Q2") (pin "1") (pinfunction "S_1") (pintype "passive"))
      (node (ref "R11") (pin "2") (pinfunction "2_2") (pintype "passive"))
      (node (ref "R14") (pin "2") (pinfunction "2_2") (pintype "passive"))
      (node (ref "R16") (pin "2") (pinfunction "2_2") (pintype "passive"))
      (node (ref "R17") (pin "2") (pinfunction "2_2") (pintype "passive"))
      (node (ref "R21") (pin "1") (pinfunction "1_1") (pintype "passive"))
      (node (ref "R22") (pin "1") (pinfunction "1_1") (pintype "passive"))
      (node (ref "R23") (pin "1") (pinfunction "1_1") (pintype "passive"))
      (node (ref "R4") (pin "2") (pinfunction "2_2") (pintype "passive"))
      (node (ref "S1") (pin "1") (pinfunction "P_1") (pintype "passive"))
      (node (ref "S2") (pin "1") (pinfunction "P_1") (pintype "passive"))
      (node (ref "S3") (pin "2") (pinfunction "P1_2") (pintype "passive"))
      (node (ref "U1") (pin "1") (pinfunction "GND1_1") (pintype "bidirectional"))
      (node (ref "U1") (pin "10") (pinfunction "GND6_10") (pintype "bidirectional"))
      (node (ref "U1") (pin "19") (pinfunction "GND7_19") (pintype "bidirectional"))
      (node (ref "U1") (pin "2") (pinfunction "GND2_2") (pintype "bidirectional"))
      (node (ref "U1") (pin "26") (pinfunction "GND8_26") (pintype "bidirectional"))
      (node (ref "U1") (pin "27") (pinfunction "GND9_27") (pintype "bidirectional"))
      (node (ref "U1") (pin "28") (pinfunction "GND10_28") (pintype "bidirectional"))
      (node (ref "U1") (pin "3") (pinfunction "GND3_3") (pintype "bidirectional"))
      (node (ref "U1") (pin "4") (pinfunction "GND4_4") (pintype "bidirectional"))
      (node (ref "U1") (pin "7") (pinfunction "GND5_7") (pintype "bidirectional"))
      (node (ref "U3") (pin "P3") (pinfunction "GND_P3") (pintype "bidirectional"))
      (node (ref "U4") (pin "3") (pinfunction "GND_3") (pintype "power_in"))
      (node (ref "U6") (pin "4") (pinfunction "GND_4") (pintype "power_in"))
      (node (ref "U7") (pin "6") (pinfunction "GND1_6") (pintype "bidirectional"))
      (node (ref "U7") (pin "7") (pinfunction "GND2_7") (pintype "bidirectional"))
      (node (ref "U7") (pin "9") (pinfunction "GND3_9") (pintype "bidirectional"))
      (node (ref "U8") (pin "3") (pinfunction "GNDANA_3") (pintype "bidirectional"))
      (node (ref "U8") (pin "35") (pinfunction "GND1_35") (pintype "bidirectional"))
      (node (ref "U8") (pin "46") (pinfunction "GNDBU_46") (pintype "bidirectional"))
      (node (ref "U8") (pin "61") (pinfunction "GND2_61") (pintype "bidirectional"))
      (node (ref "U8") (pin "72") (pinfunction "GNDPLL_72") (pintype "bidirectional"))
      (node (ref "U8") (pin "82") (pinfunction "GNDUTMI_82") (pintype "bidirectional"))
      (node (ref "U8") (pin "89") (pinfunction "GND3_89") (pintype "bidirectional"))
    )
    (net (code "48") (name "Net-(C1-3)") (class "Default")
      (node (ref "C1") (pin "2") (pinfunction "3_2") (pintype "passive"))
      (node (ref "J26") (pin "1") (pinfunction "1_1") (pintype "passive"))
      (node (ref "X1") (pin "1") (pinfunction "1_1") (pintype "passive"))
    )
    (net (code "49") (name "Net-(C2-3)") (class "Default")
      (node (ref "C2") (pin "2") (pinfunction "3_2") (pintype "passive"))
      (node (ref "J27") (pin "1") (pinfunction "1_1") (pintype "passive"))
      (node (ref "X1") (pin "2") (pinfunction "2_2") (pintype "passive"))
    )
    (net (code "50") (name "Net-(C4-3)") (class "Default")
      (node (ref "C4") (pin "2") (pinfunction "3_2") (pintype "passive"))
      (node (ref "JP6") (pin "1") (pinfunction "1_1") (pintype "passive"))
      (node (ref "U6") (pin "3") (pinfunction "~{WP}_3") (pintype "input"))
      (node (ref "U6") (pin "7") (pinfunction "~{HOLD}_7") (pintype "input"))
      (node (ref "U6") (pin "8") (pinfunction "VCC_8") (pintype "power_in"))
    )
    (net (code "51") (name "Net-(C12-3)") (class "Default")
      (node (ref "C12") (pin "2") (pinfunction "3_2") (pintype "passive"))
      (node (ref "C5") (pin "2") (pinfunction "3_2") (pintype "passive"))
      (node (ref "JP7") (pin "1") (pinfunction "1_1") (pintype "passive"))
      (node (ref "R24") (pin "2") (pinfunction "2_2") (pintype "passive"))
      (node (ref "R25") (pin "2") (pinfunction "2_2") (pintype "passive"))
      (node (ref "U7") (pin "1") (pinfunction "VDD_1") (pintype "bidirectional"))
      (node (ref "U7") (pin "8") (pinfunction "VDDIO_8") (pintype "bidirectional"))
    )
    (net (code "52") (name "Net-(C18-3)") (class "Default")
      (node (ref "C18") (pin "2") (pinfunction "3_2") (pintype "passive"))
      (node (ref "U7") (pin "4") (pinfunction "BYP_4") (pintype "bidirectional"))
    )
    (net (code "53") (name "Net-(C20-3)") (class "Default")
      (node (ref "C20") (pin "2") (pinfunction "3_2") (pintype "passive"))
      (node (ref "U8") (pin "74") (pinfunction "XOUT_74") (pintype "bidirectional"))
      (node (ref "X2") (pin "1") (pinfunction "1_1") (pintype "passive"))
    )
    (net (code "54") (name "Net-(C21-3)") (class "Default")
      (node (ref "C21") (pin "2") (pinfunction "3_2") (pintype "passive"))
      (node (ref "U8") (pin "75") (pinfunction "XIN_75") (pintype "bidirectional"))
      (node (ref "X2") (pin "3") (pinfunction "2_3") (pintype "passive"))
    )
    (net (code "55") (name "Net-(C25-3)") (class "Default")
      (node (ref "C25") (pin "2") (pinfunction "3_2") (pintype "passive"))
      (node (ref "R17") (pin "1") (pinfunction "1_1") (pintype "passive"))
      (node (ref "U8") (pin "78") (pinfunction "VBG_78") (pintype "bidirectional"))
    )
    (net (code "56") (name "Net-(D4-CBLUE)") (class "Default")
      (node (ref "D4") (pin "3") (pinfunction "CBLUE_3") (pintype "passive"))
      (node (ref "R2") (pin "2") (pinfunction "2_2") (pintype "passive"))
    )
    (net (code "57") (name "Net-(D4-CGREEN)") (class "Default")
      (node (ref "D4") (pin "4") (pinfunction "CGREEN_4") (pintype "passive"))
      (node (ref "R3") (pin "2") (pinfunction "2_2") (pintype "passive"))
    )
    (net (code "58") (name "Net-(D4-CRED)") (class "Default")
      (node (ref "D4") (pin "1") (pinfunction "CRED_1") (pintype "passive"))
      (node (ref "R1") (pin "2") (pinfunction "2_2") (pintype "passive"))
    )
    (net (code "59") (name "Net-(D5-PadA)") (class "Default")
      (node (ref "D5") (pin "A") (pinfunction "A_A") (pintype "passive"))
      (node (ref "R13") (pin "1") (pinfunction "1_1") (pintype "passive"))
    )
    (net (code "60") (name "Net-(D6-PadA)") (class "Default")
      (node (ref "D6") (pin "A") (pinfunction "A_A") (pintype "passive"))
      (node (ref "R18") (pin "1") (pinfunction "1_1") (pintype "passive"))
    )
    (net (code "61") (name "Net-(JP21-Pad2)") (class "Default")
      (node (ref "JP21") (pin "2") (pinfunction "2_2") (pintype "passive"))
      (node (ref "R29") (pin "1") (pinfunction "1_1") (pintype "passive"))
    )
    (net (code "62") (name "Net-(Q1A-D)") (class "Default")
      (node (ref "Q1") (pin "6") (pinfunction "D_6") (pintype "passive"))
      (node (ref "R2") (pin "1") (pinfunction "1_1") (pintype "passive"))
    )
    (net (code "63") (name "Net-(Q1B-D)") (class "Default")
      (node (ref "Q1") (pin "3") (pinfunction "D_3") (pintype "passive"))
      (node (ref "R3") (pin "1") (pinfunction "1_1") (pintype "passive"))
    )
    (net (code "64") (name "Net-(Q2A-D)") (class "Default")
      (node (ref "Q2") (pin "6") (pinfunction "D_6") (pintype "passive"))
      (node (ref "R1") (pin "1") (pinfunction "1_1") (pintype "passive"))
    )
    (net (code "65") (name "Net-(S3-S1)") (class "Default")
      (node (ref "D3") (pin "C") (pinfunction "C_C") (pintype "passive"))
      (node (ref "R29") (pin "2") (pinfunction "2_2") (pintype "passive"))
      (node (ref "S3") (pin "4") (pinfunction "S1_4") (pintype "passive"))
    )
    (net (code "66") (name "Net-(U1-P0.26)") (class "Default")
      (node (ref "J26") (pin "2") (pinfunction "2_2") (pintype "passive"))
      (node (ref "U1") (pin "8") (pinfunction "P0.26_8") (pintype "bidirectional"))
    )
    (net (code "67") (name "Net-(U1-P0.27)") (class "Default")
      (node (ref "J27") (pin "2") (pinfunction "2_2") (pintype "passive"))
      (node (ref "U1") (pin "9") (pinfunction "P0.27_9") (pintype "bidirectional"))
    )
    (net (code "68") (name "Net-(U1-VCC)") (class "Default")
      (node (ref "C7") (pin "1") (pinfunction "1_1") (pintype "passive"))
      (node (ref "JCUR") (pin "2") (pinfunction "2_2") (pintype "passive"))
      (node (ref "R20") (pin "2") (pinfunction "2_2") (pintype "passive"))
      (node (ref "U1") (pin "18") (pinfunction "VCC_18") (pintype "bidirectional"))
    )
    (net (code "69") (name "Net-(U2-VCC)") (class "Default")
      (node (ref "JP2") (pin "2") (pinfunction "2_2") (pintype "passive"))
      (node (ref "U2") (pin "1") (pinfunction "VCC_1") (pintype "power_in"))
    )
    (net (code "70") (name "Net-(U3-IO1)") (class "Default")
      (node (ref "JUSB") (pin "D+") (pinfunction "D+_D+") (pintype "bidirectional"))
      (node (ref "R7") (pin "1") (pinfunction "1_1") (pintype "passive"))
      (node (ref "U3") (pin "P1") (pinfunction "IO1_P1") (pintype "bidirectional"))
      (node (ref "U8") (pin "76") (pinfunction "DHSDP_76") (pintype "bidirectional"))
    )
    (net (code "71") (name "Net-(U3-IO2)") (class "Default")
      (node (ref "JUSB") (pin "D-") (pinfunction "D-_D-") (pintype "bidirectional"))
      (node (ref "R8") (pin "1") (pinfunction "1_1") (pintype "passive"))
      (node (ref "U3") (pin "P2") (pinfunction "IO2_P2") (pintype "bidirectional"))
      (node (ref "U8") (pin "77") (pinfunction "DHSDM_77") (pintype "bidirectional"))
    )
    (net (code "72") (name "Net-(U8-DFSDM)") (class "Default")
      (node (ref "R8") (pin "2") (pinfunction "2_2") (pintype "passive"))
      (node (ref "U8") (pin "80") (pinfunction "DFSDM_80") (pintype "bidirectional"))
    )
    (net (code "73") (name "Net-(U8-DFSDP)") (class "Default")
      (node (ref "R7") (pin "2") (pinfunction "2_2") (pintype "passive"))
      (node (ref "U8") (pin "81") (pinfunction "DFSDP_81") (pintype "bidirectional"))
    )
    (net (code "74") (name "Net-(U8-ERASE)") (class "Default")
      (node (ref "R4") (pin "1") (pinfunction "1_1") (pintype "passive"))
      (node (ref "U8") (pin "43") (pinfunction "ERASE_43") (pintype "bidirectional"))
    )
    (net (code "75") (name "Net-(U8-NRSTB)") (class "Default")
      (node (ref "C19") (pin "1") (pinfunction "1_1") (pintype "passive"))
      (node (ref "R12") (pin "1") (pinfunction "1_1") (pintype "passive"))
      (node (ref "U8") (pin "47") (pinfunction "NRSTB_47") (pintype "bidirectional"))
    )
    (net (code "76") (name "Net-(U8-PA0)") (class "Default")
      (node (ref "R5") (pin "1") (pinfunction "1_1") (pintype "passive"))
      (node (ref "U8") (pin "26") (pinfunction "PA0_26") (pintype "bidirectional"))
    )
    (net (code "77") (name "Net-(U8-PA1)") (class "Default")
      (node (ref "R5") (pin "2") (pinfunction "2_2") (pintype "passive"))
      (node (ref "U8") (pin "27") (pinfunction "PA1_27") (pintype "bidirectional"))
    )
    (net (code "78") (name "Net-(U8-PA3)") (class "Default")
      (node (ref "R6") (pin "1") (pinfunction "1_1") (pintype "passive"))
      (node (ref "U8") (pin "29") (pinfunction "PA3_29") (pintype "bidirectional"))
    )
    (net (code "79") (name "Net-(U8-PA4)") (class "Default")
      (node (ref "R6") (pin "2") (pinfunction "2_2") (pintype "passive"))
      (node (ref "U8") (pin "30") (pinfunction "PA4_30") (pintype "bidirectional"))
    )
    (net (code "80") (name "Net-(U8-PA13)") (class "Default")
      (node (ref "R28") (pin "1") (pinfunction "1_1") (pintype "passive"))
      (node (ref "U8") (pin "10") (pinfunction "PA13_10") (pintype "bidirectional"))
    )
    (net (code "81") (name "Net-(U8-PA17)") (class "Default")
      (node (ref "R27") (pin "2") (pinfunction "2_2") (pintype "passive"))
      (node (ref "U8") (pin "14") (pinfunction "PA17_14") (pintype "bidirectional"))
      (node (ref "U8") (pin "23") (pinfunction "PA24_23") (pintype "bidirectional"))
    )
    (net (code "82") (name "Net-(U8-PA18)") (class "Default")
      (node (ref "R26") (pin "2") (pinfunction "2_2") (pintype "passive"))
      (node (ref "U8") (pin "17") (pinfunction "PA18_17") (pintype "bidirectional"))
    )
    (net (code "83") (name "Net-(U8-PA20)") (class "Default")
      (node (ref "R28") (pin "2") (pinfunction "2_2") (pintype "passive"))
      (node (ref "U8") (pin "19") (pinfunction "PA20_19") (pintype "bidirectional"))
    )
    (net (code "84") (name "Net-(U8-PA26)") (class "Default")
      (node (ref "JP26") (pin "1") (pinfunction "1_1") (pintype "passive"))
      (node (ref "U8") (pin "25") (pinfunction "PA26_25") (pintype "bidirectional"))
    )
    (net (code "85") (name "VBATT") (class "Default")
      (node (ref "BAT") (pin "BAT+1") (pinfunction "+_BAT+1") (pintype "bidirectional"))
      (node (ref "BAT") (pin "BAT+2") (pinfunction "+_BAT+2") (pintype "bidirectional"))
      (node (ref "D8") (pin "A") (pinfunction "A_A") (pintype "passive"))
      (node (ref "JBAT") (pin "1") (pinfunction "1_1") (pintype "passive"))
    )
    (net (code "86") (name "VCORE") (class "Default")
      (node (ref "C23") (pin "2") (pinfunction "3_2") (pintype "passive"))
      (node (ref "C26") (pin "2") (pinfunction "3_2") (pintype "passive"))
      (node (ref "C27") (pin "2") (pinfunction "3_2") (pintype "passive"))
      (node (ref "C28") (pin "2") (pinfunction "3_2") (pintype "passive"))
      (node (ref "C29") (pin "2") (pinfunction "3_2") (pintype "passive"))
      (node (ref "C30") (pin "2") (pinfunction "3_2") (pintype "passive"))
      (node (ref "C38") (pin "2") (pinfunction "3_2") (pintype "passive"))
      (node (ref "U8") (pin "34") (pinfunction "VDDCORE2_34") (pintype "bidirectional"))
      (node (ref "U8") (pin "52") (pinfunction "VDDOUT_52") (pintype "bidirectional"))
      (node (ref "U8") (pin "59") (pinfunction "VDDCORE3_59") (pintype "bidirectional"))
      (node (ref "U8") (pin "73") (pinfunction "VDDPLL_73") (pintype "bidirectional"))
      (node (ref "U8") (pin "83") (pinfunction "VDDCORE4_83") (pintype "bidirectional"))
      (node (ref "U8") (pin "87") (pinfunction "VDDCORE5_87") (pintype "bidirectional"))
      (node (ref "U8") (pin "9") (pinfunction "VDDCORE1_9") (pintype "bidirectional"))
    )
    (net (code "87") (name "VSYS") (class "Default")
      (node (ref "A1") (pin "2") (pinfunction "2_2") (pintype "passive"))
      (node (ref "B1") (pin "1") (pinfunction "1_1") (pintype "passive"))
      (node (ref "C22") (pin "2") (pinfunction "3_2") (pintype "passive"))
      (node (ref "C24") (pin "2") (pinfunction "3_2") (pintype "passive"))
      (node (ref "C31") (pin "2") (pinfunction "3_2") (pintype "passive"))
      (node (ref "C32") (pin "2") (pinfunction "3_2") (pintype "passive"))
      (node (ref "C33") (pin "2") (pinfunction "3_2") (pintype "passive"))
      (node (ref "C34") (pin "2") (pinfunction "3_2") (pintype "passive"))
      (node (ref "C35") (pin "2") (pinfunction "3_2") (pintype "passive"))
      (node (ref "C36") (pin "2") (pinfunction "3_2") (pintype "passive"))
      (node (ref "C37") (pin "2") (pinfunction "3_2") (pintype "passive"))
      (node (ref "D4") (pin "2") (pinfunction "A2_2") (pintype "passive"))
      (node (ref "D7") (pin "C") (pinfunction "C_C") (pintype "passive"))
      (node (ref "D8") (pin "C") (pinfunction "C_C") (pintype "passive"))
      (node (ref "J3V3") (pin "1") (pinfunction "1_1") (pintype "passive"))
      (node (ref "JBAT") (pin "2") (pinfunction "2_2") (pintype "passive"))
      (node (ref "JCUR") (pin "1") (pinfunction "1_1") (pintype "passive"))
      (node (ref "JP2") (pin "1") (pinfunction "1_1") (pintype "passive"))
      (node (ref "JP6") (pin "2") (pinfunction "2_2") (pintype "passive"))
      (node (ref "JP7") (pin "2") (pinfunction "2_2") (pintype "passive"))
      (node (ref "JTAG") (pin "1") (pinfunction "1_1") (pintype "passive"))
      (node (ref "R10") (pin "1") (pinfunction "1_1") (pintype "passive"))
      (node (ref "R13") (pin "2") (pinfunction "2_2") (pintype "passive"))
      (node (ref "R15") (pin "1") (pinfunction "1_1") (pintype "passive"))
      (node (ref "R18") (pin "2") (pinfunction "2_2") (pintype "passive"))
      (node (ref "R20") (pin "1") (pinfunction "1_1") (pintype "passive"))
      (node (ref "R9") (pin "1") (pinfunction "1_1") (pintype "passive"))
      (node (ref "U8") (pin "1") (pinfunction "VDDANA_1") (pintype "bidirectional"))
      (node (ref "U8") (pin "2") (pinfunction "ADVREF_2") (pintype "bidirectional"))
      (node (ref "U8") (pin "22") (pinfunction "VDDIO1_22") (pintype "bidirectional"))
      (node (ref "U8") (pin "36") (pinfunction "VDDIO2_36") (pintype "bidirectional"))
      (node (ref "U8") (pin "42") (pinfunction "FWUP_42") (pintype "bidirectional"))
      (node (ref "U8") (pin "45") (pinfunction "VDDBU_45") (pintype "bidirectional"))
      (node (ref "U8") (pin "53") (pinfunction "VDDIN_53") (pintype "bidirectional"))
      (node (ref "U8") (pin "60") (pinfunction "VDDIO3_60") (pintype "bidirectional"))
      (node (ref "U8") (pin "79") (pinfunction "VDDUTMI_79") (pintype "bidirectional"))
      (node (ref "U8") (pin "88") (pinfunction "VDDIO4_88") (pintype "bidirectional"))
    )
    (net (code "88") (name "VUSB") (class "Default")
      (node (ref "A1") (pin "1") (pinfunction "1_1") (pintype "passive"))
      (node (ref "C10") (pin "2") (pinfunction "3_2") (pintype "passive"))
      (node (ref "C3") (pin "2") (pinfunction "3_2") (pintype "passive"))
      (node (ref "C6") (pin "1") (pinfunction "1_1") (pintype "passive"))
      (node (ref "JTAG") (pin "5") (pinfunction "5_5") (pintype "passive"))
      (node (ref "JUSB") (pin "VBUS") (pinfunction "VBUS_VBUS") (pintype "bidirectional"))
      (node (ref "U3") (pin "P5") (pinfunction "VCC_P5") (pintype "bidirectional"))
      (node (ref "U4") (pin "1") (pinfunction "IN_1") (pintype "power_in"))
    )
    (net (code "89") (name "unconnected-(JTAG-Pad7)") (class "Default")
      (node (ref "JTAG") (pin "7") (pinfunction "7_7") (pintype "passive"))
    )
    (net (code "90") (name "unconnected-(JTAG-Pad9)") (class "Default")
      (node (ref "JTAG") (pin "9") (pinfunction "9_9") (pintype "passive"))
    )
    (net (code "91") (name "unconnected-(S1-P1-Pad2)") (class "Default")
      (node (ref "S1") (pin "2") (pinfunction "P1_2") (pintype "passive"))
    )
    (net (code "92") (name "unconnected-(S1-S1-Pad4)") (class "Default")
      (node (ref "S1") (pin "4") (pinfunction "S1_4") (pintype "passive"))
    )
    (net (code "93") (name "unconnected-(S2-P1-Pad2)") (class "Default")
      (node (ref "S2") (pin "2") (pinfunction "P1_2") (pintype "passive"))
    )
    (net (code "94") (name "unconnected-(S2-S1-Pad4)") (class "Default")
      (node (ref "S2") (pin "4") (pinfunction "S1_4") (pintype "passive"))
    )
    (net (code "95") (name "unconnected-(S3-P-Pad1)") (class "Default")
      (node (ref "S3") (pin "1") (pinfunction "P_1") (pintype "passive"))
    )
    (net (code "96") (name "unconnected-(S3-S-Pad3)") (class "Default")
      (node (ref "S3") (pin "3") (pinfunction "S_3") (pintype "passive"))
    )
    (net (code "97") (name "unconnected-(U3-IO3-PadP4)") (class "Default")
      (node (ref "U3") (pin "P4") (pinfunction "IO3_P4") (pintype "bidirectional"))
    )
    (net (code "98") (name "unconnected-(U7-INT2-Pad5)") (class "Default")
      (node (ref "U7") (pin "5") (pinfunction "INT2_5") (pintype "bidirectional"))
    )
    (net (code "99") (name "unconnected-(U8-AD12BVREF-Pad4)") (class "Default")
      (node (ref "U8") (pin "4") (pinfunction "AD12BVREF_4") (pintype "bidirectional"))
    )
    (net (code "100") (name "unconnected-(U8-JTAGSEL-Pad48)") (class "Default")
      (node (ref "U8") (pin "48") (pinfunction "JTAGSEL_48") (pintype "bidirectional"))
    )
    (net (code "101") (name "unconnected-(U8-PA2-Pad28)") (class "Default")
      (node (ref "U8") (pin "28") (pinfunction "PA2_28") (pintype "bidirectional"))
    )
    (net (code "102") (name "unconnected-(U8-PA5-Pad31)") (class "Default")
      (node (ref "U8") (pin "31") (pinfunction "PA5_31") (pintype "bidirectional"))
    )
    (net (code "103") (name "unconnected-(U8-PA6-Pad32)") (class "Default")
      (node (ref "U8") (pin "32") (pinfunction "PA6_32") (pintype "bidirectional"))
    )
    (net (code "104") (name "unconnected-(U8-PA7-Pad33)") (class "Default")
      (node (ref "U8") (pin "33") (pinfunction "PA7_33") (pintype "bidirectional"))
    )
    (net (code "105") (name "unconnected-(U8-PA8-Pad37)") (class "Default")
      (node (ref "U8") (pin "37") (pinfunction "PA8_37") (pintype "bidirectional"))
    )
    (net (code "106") (name "unconnected-(U8-PA14-Pad11)") (class "Default")
      (node (ref "U8") (pin "11") (pinfunction "PA14_11") (pintype "bidirectional"))
    )
    (net (code "107") (name "unconnected-(U8-PA16-Pad13)") (class "Default")
      (node (ref "U8") (pin "13") (pinfunction "PA16_13") (pintype "bidirectional"))
    )
    (net (code "108") (name "unconnected-(U8-PA19-Pad18)") (class "Default")
      (node (ref "U8") (pin "18") (pinfunction "PA19_18") (pintype "bidirectional"))
    )
    (net (code "109") (name "unconnected-(U8-PA21-Pad20)") (class "Default")
      (node (ref "U8") (pin "20") (pinfunction "PA21_20") (pintype "bidirectional"))
    )
    (net (code "110") (name "unconnected-(U8-PA27-Pad96)") (class "Default")
      (node (ref "U8") (pin "96") (pinfunction "PA27_96") (pintype "bidirectional"))
    )
    (net (code "111") (name "unconnected-(U8-PA30-Pad6)") (class "Default")
      (node (ref "U8") (pin "6") (pinfunction "PA30_6") (pintype "bidirectional"))
    )
    (net (code "112") (name "unconnected-(U8-PA31-Pad86)") (class "Default")
      (node (ref "U8") (pin "86") (pinfunction "PA31_86") (pintype "bidirectional"))
    )
    (net (code "113") (name "unconnected-(U8-PB0-Pad90)") (class "Default")
      (node (ref "U8") (pin "90") (pinfunction "PB0_90") (pintype "bidirectional"))
    )
    (net (code "114") (name "unconnected-(U8-PB1-Pad91)") (class "Default")
      (node (ref "U8") (pin "91") (pinfunction "PB1_91") (pintype "bidirectional"))
    )
    (net (code "115") (name "unconnected-(U8-PB2-Pad92)") (class "Default")
      (node (ref "U8") (pin "92") (pinfunction "PB2_92") (pintype "bidirectional"))
    )
    (net (code "116") (name "unconnected-(U8-PB3-Pad7)") (class "Default")
      (node (ref "U8") (pin "7") (pinfunction "PB3_7") (pintype "bidirectional"))
    )
    (net (code "117") (name "unconnected-(U8-PB4-Pad8)") (class "Default")
      (node (ref "U8") (pin "8") (pinfunction "PB4_8") (pintype "bidirectional"))
    )
    (net (code "118") (name "unconnected-(U8-PB5-Pad97)") (class "Default")
      (node (ref "U8") (pin "97") (pinfunction "PB5_97") (pintype "bidirectional"))
    )
    (net (code "119") (name "unconnected-(U8-PB6-Pad98)") (class "Default")
      (node (ref "U8") (pin "98") (pinfunction "PB6_98") (pintype "bidirectional"))
    )
    (net (code "120") (name "unconnected-(U8-PB8-Pad100)") (class "Default")
      (node (ref "U8") (pin "100") (pinfunction "PB8_100") (pintype "bidirectional"))
    )
    (net (code "121") (name "unconnected-(U8-PB9-Pad71)") (class "Default")
      (node (ref "U8") (pin "71") (pinfunction "PB9_71") (pintype "bidirectional"))
    )
    (net (code "122") (name "unconnected-(U8-PB10-Pad70)") (class "Default")
      (node (ref "U8") (pin "70") (pinfunction "PB10_70") (pintype "bidirectional"))
    )
    (net (code "123") (name "unconnected-(U8-PB11-Pad93)") (class "Default")
      (node (ref "U8") (pin "93") (pinfunction "PB11_93") (pintype "bidirectional"))
    )
    (net (code "124") (name "unconnected-(U8-PB12-Pad94)") (class "Default")
      (node (ref "U8") (pin "94") (pinfunction "PB12_94") (pintype "bidirectional"))
    )
    (net (code "125") (name "unconnected-(U8-PB13-Pad95)") (class "Default")
      (node (ref "U8") (pin "95") (pinfunction "PB13_95") (pintype "bidirectional"))
    )
    (net (code "126") (name "unconnected-(U8-PB14-Pad69)") (class "Default")
      (node (ref "U8") (pin "69") (pinfunction "PB14_69") (pintype "bidirectional"))
    )
    (net (code "127") (name "unconnected-(U8-PB15-Pad16)") (class "Default")
      (node (ref "U8") (pin "16") (pinfunction "PB15_16") (pintype "bidirectional"))
    )
    (net (code "128") (name "unconnected-(U8-PB16-Pad15)") (class "Default")
      (node (ref "U8") (pin "15") (pinfunction "PB16_15") (pintype "bidirectional"))
    )
    (net (code "129") (name "unconnected-(U8-PB17-Pad68)") (class "Default")
      (node (ref "U8") (pin "68") (pinfunction "PB17_68") (pintype "bidirectional"))
    )
    (net (code "130") (name "unconnected-(U8-PB18-Pad67)") (class "Default")
      (node (ref "U8") (pin "67") (pinfunction "PB18_67") (pintype "bidirectional"))
    )
    (net (code "131") (name "unconnected-(U8-PB19-Pad66)") (class "Default")
      (node (ref "U8") (pin "66") (pinfunction "PB19_66") (pintype "bidirectional"))
    )
    (net (code "132") (name "unconnected-(U8-PB20-Pad65)") (class "Default")
      (node (ref "U8") (pin "65") (pinfunction "PB20_65") (pintype "bidirectional"))
    )
    (net (code "133") (name "unconnected-(U8-PB21-Pad64)") (class "Default")
      (node (ref "U8") (pin "64") (pinfunction "PB21_64") (pintype "bidirectional"))
    )
    (net (code "134") (name "unconnected-(U8-PB22-Pad63)") (class "Default")
      (node (ref "U8") (pin "63") (pinfunction "PB22_63") (pintype "bidirectional"))
    )
    (net (code "135") (name "unconnected-(U8-PB23-Pad62)") (class "Default")
      (node (ref "U8") (pin "62") (pinfunction "PB23_62") (pintype "bidirectional"))
    )
    (net (code "136") (name "unconnected-(U8-PB24-Pad58)") (class "Default")
      (node (ref "U8") (pin "58") (pinfunction "PB24_58") (pintype "bidirectional"))
    )
    (net (code "137") (name "unconnected-(U8-TEST-Pad44)") (class "Default")
      (node (ref "U8") (pin "44") (pinfunction "TEST_44") (pintype "bidirectional"))
    )
    (net (code "138") (name "unconnected-(U8-XIN32-Pad50)") (class "Default")
      (node (ref "U8") (pin "50") (pinfunction "XIN32_50") (pintype "bidirectional"))
    )
    (net (code "139") (name "unconnected-(U8-XOUT32-Pad49)") (class "Default")
      (node (ref "U8") (pin "49") (pinfunction "XOUT32_49") (pintype "bidirectional"))
    )
  )
)
